# FPGA_POWER_DGND.net
KiCad netlist of a schematic drawn in Altium Designer
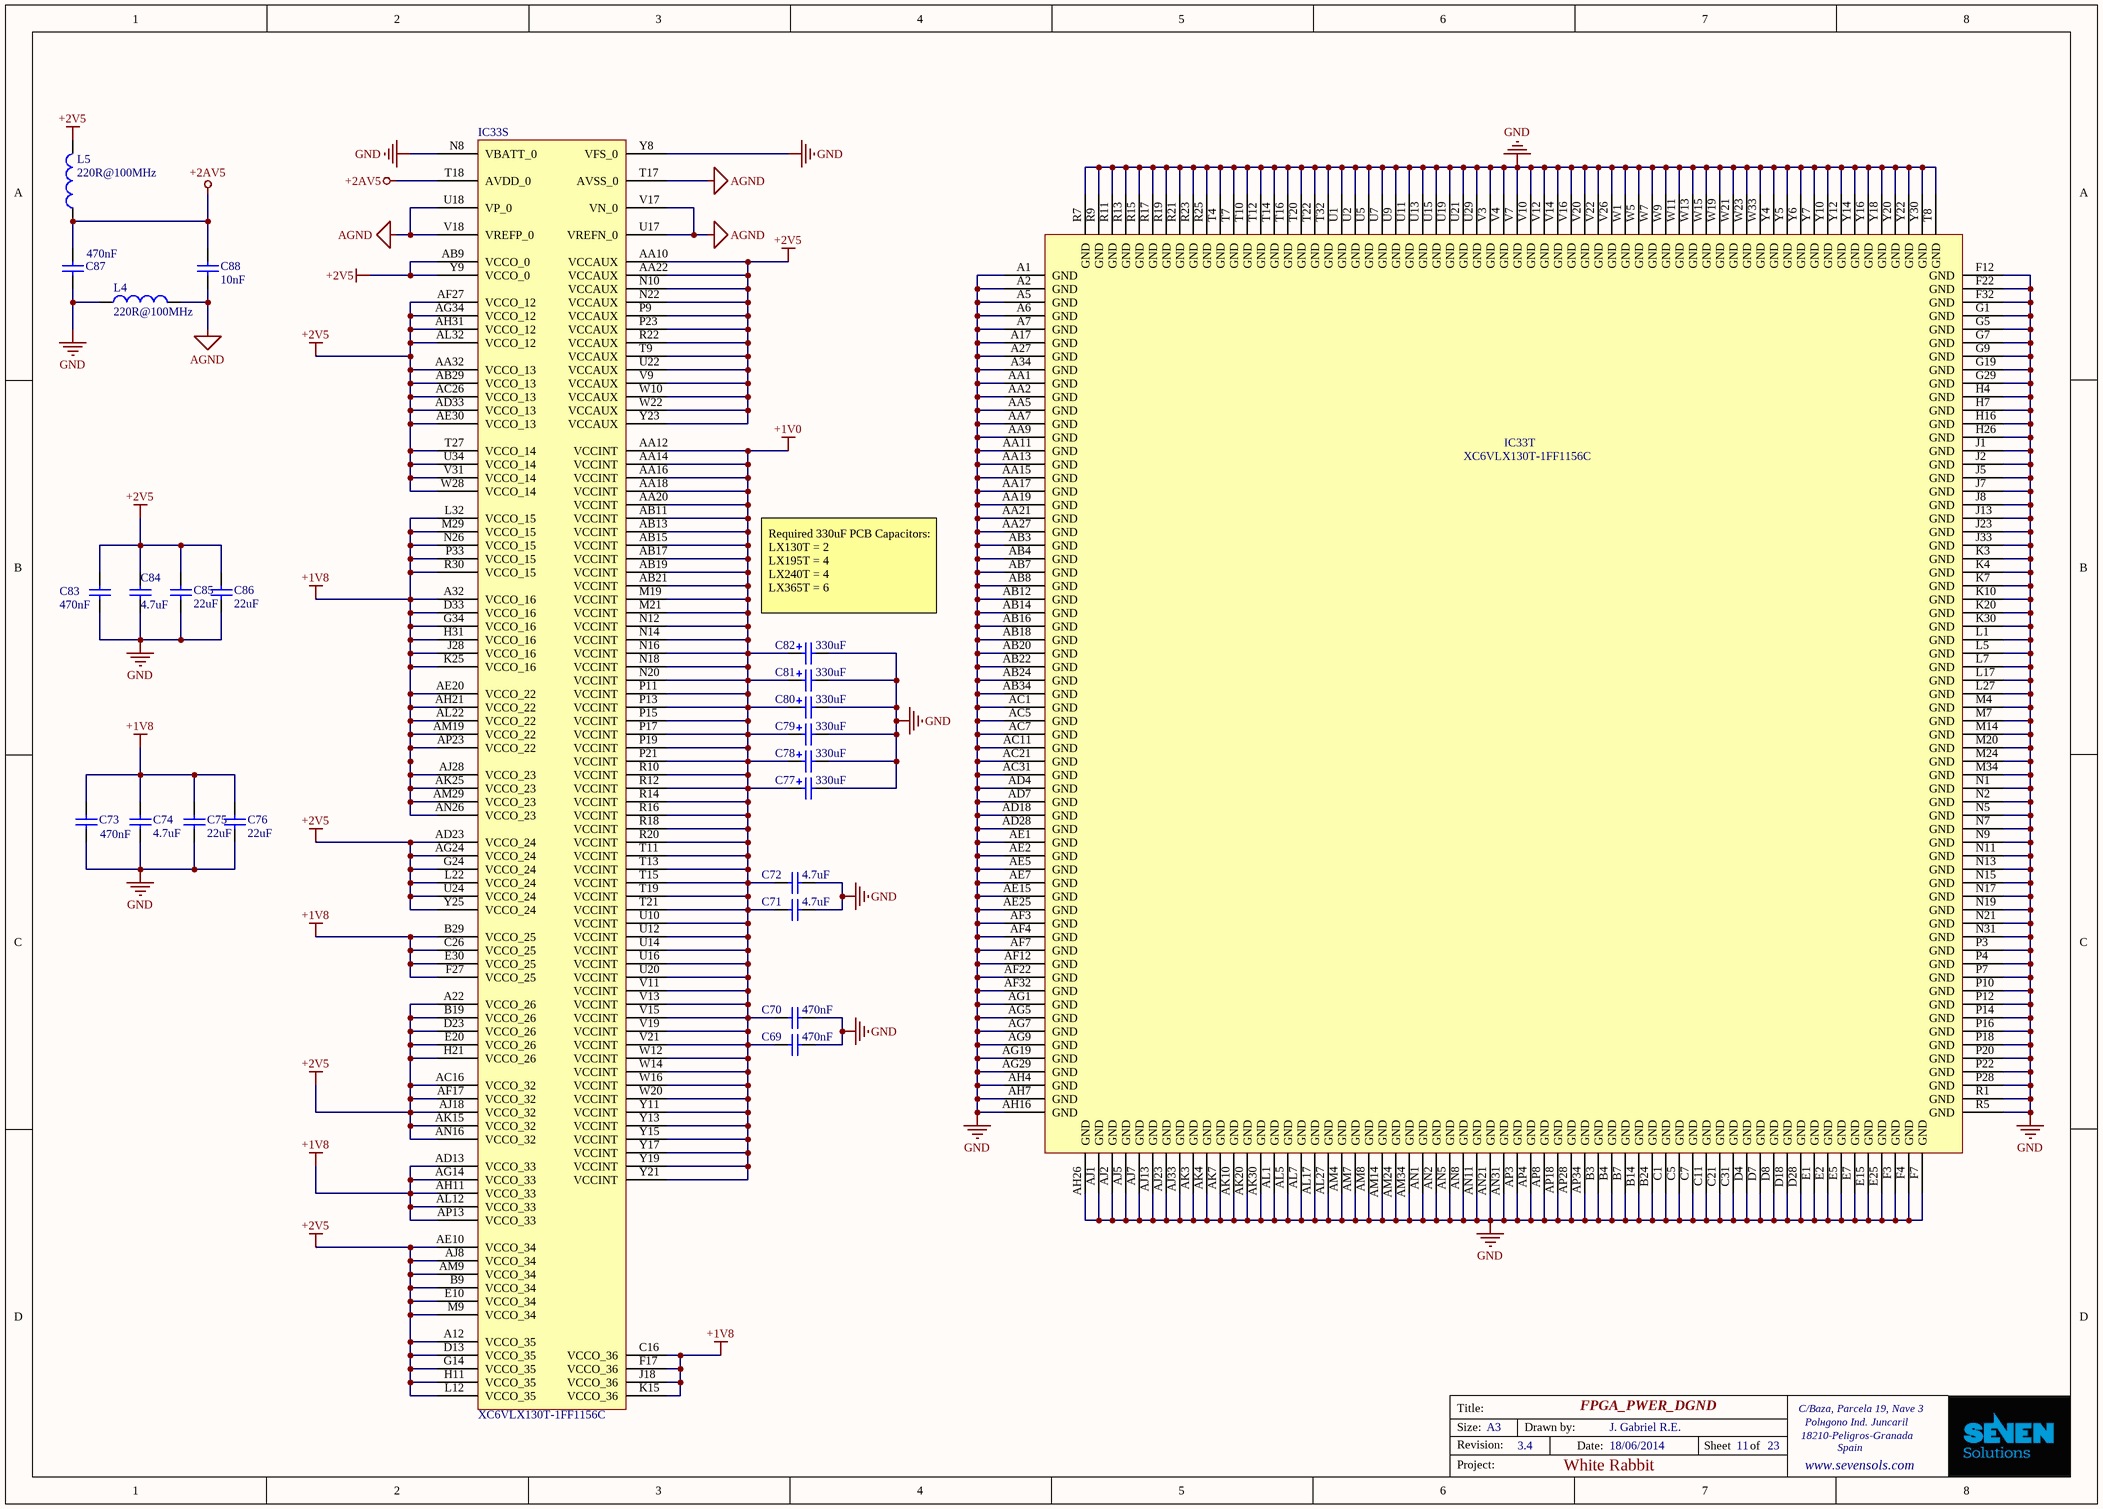
[diagram p0: FPGA_POWER_DGND.SchDoc]

(export (version "E")
  (design (tool "Eeschema 10.0.6"))
  (components
    (comp (ref "C69")
      (value "470nF")
      (footprint "CC1005-0402")
      (description "Capacitor")
      (fields
        (field (name "TOLERANCE") "±10%")
        (field (name "VOLTAGE") "16V")
        (field (name "PUBLISHER") "Altium Limited")
      )
      (libsource (lib "wr_switch") (part "Cap"))
    )
    (comp (ref "C70")
      (value "470nF")
      (footprint "CC1005-0402")
      (description "Capacitor")
      (fields
        (field (name "TOLERANCE") "±10%")
        (field (name "VOLTAGE") "16V")
        (field (name "PUBLISHER") "Altium Limited")
      )
      (libsource (lib "wr_switch") (part "Cap"))
    )
    (comp (ref "C71")
      (value "4.7uF")
      (footprint "CC1608-0603")
      (description "Capacitor")
      (fields
        (field (name "TOLERANCE") "±10%")
        (field (name "VOLTAGE") "10V")
        (field (name "PUBLISHER") "Altium Limited")
      )
      (libsource (lib "wr_switch") (part "Cap"))
    )
    (comp (ref "C72")
      (value "4.7uF")
      (footprint "CC1608-0603")
      (description "Capacitor")
      (fields
        (field (name "TOLERANCE") "±10%")
        (field (name "VOLTAGE") "10V")
        (field (name "PUBLISHER") "Altium Limited")
      )
      (libsource (lib "wr_switch") (part "Cap"))
    )
    (comp (ref "C73")
      (value "470nF")
      (footprint "CC1005-0402")
      (description "Capacitor")
      (fields
        (field (name "TOLERANCE") "±10%")
        (field (name "VOLTAGE") "16V")
        (field (name "PUBLISHER") "Altium Limited")
      )
      (libsource (lib "wr_switch") (part "Cap"))
    )
    (comp (ref "C74")
      (value "4.7uF")
      (footprint "CC1608-0603")
      (description "Capacitor")
      (fields
        (field (name "TOLERANCE") "±10%")
        (field (name "VOLTAGE") "10V")
        (field (name "PUBLISHER") "Altium Limited")
      )
      (libsource (lib "wr_switch") (part "Cap"))
    )
    (comp (ref "C75")
      (value "22uF")
      (footprint "CC2012-0805")
      (description "Capacitor")
      (fields
        (field (name "TOLERANCE") "±20%")
        (field (name "VOLTAGE") "6.3V")
        (field (name "PUBLISHER") "Altium Limited")
      )
      (libsource (lib "wr_switch") (part "Cap"))
    )
    (comp (ref "C76")
      (value "22uF")
      (footprint "CC2012-0805")
      (description "Capacitor")
      (fields
        (field (name "TOLERANCE") "±20%")
        (field (name "VOLTAGE") "6.3V")
        (field (name "PUBLISHER") "Altium Limited")
      )
      (libsource (lib "wr_switch") (part "Cap"))
    )
    (comp (ref "C77")
      (value "330uF")
      (footprint "D")
      (description "Polarized Capacitor Tantalum")
      (fields
        (field (name "TOLERANCE") "±20%")
        (field (name "VOLTAGE") "6.3V")
        (field (name "PUBLISHER") "Altium Limited")
      )
      (libsource (lib "wr_switch") (part "Cap Pol1"))
    )
    (comp (ref "C78")
      (value "330uF")
      (footprint "D")
      (description "Polarized Capacitor Tantalum")
      (fields
        (field (name "TOLERANCE") "±20%")
        (field (name "VOLTAGE") "6.3V")
        (field (name "PUBLISHER") "Altium Limited")
      )
      (libsource (lib "wr_switch") (part "Cap Pol1"))
    )
    (comp (ref "C79")
      (value "330uF")
      (footprint "D")
      (description "Polarized Capacitor Tantalum")
      (fields
        (field (name "TOLERANCE") "±20%")
        (field (name "VOLTAGE") "6.3V")
        (field (name "PUBLISHER") "Altium Limited")
      )
      (libsource (lib "wr_switch") (part "Cap Pol1"))
    )
    (comp (ref "C80")
      (value "330uF")
      (footprint "D")
      (description "Polarized Capacitor Tantalum")
      (fields
        (field (name "TOLERANCE") "±20%")
        (field (name "VOLTAGE") "6.3V")
        (field (name "PUBLISHER") "Altium Limited")
      )
      (libsource (lib "wr_switch") (part "Cap Pol1"))
    )
    (comp (ref "C81")
      (value "330uF")
      (footprint "D")
      (description "Polarized Capacitor Tantalum")
      (fields
        (field (name "TOLERANCE") "±20%")
        (field (name "VOLTAGE") "6.3V")
        (field (name "PUBLISHER") "Altium Limited")
      )
      (libsource (lib "wr_switch") (part "Cap Pol1"))
    )
    (comp (ref "C82")
      (value "330uF")
      (footprint "D")
      (description "Polarized Capacitor Tantalum")
      (fields
        (field (name "TOLERANCE") "±20%")
        (field (name "VOLTAGE") "6.3V")
        (field (name "PUBLISHER") "Altium Limited")
      )
      (libsource (lib "wr_switch") (part "Cap Pol1"))
    )
    (comp (ref "C83")
      (value "470nF")
      (footprint "CC1005-0402")
      (description "Capacitor")
      (fields
        (field (name "TOLERANCE") "±10%")
        (field (name "VOLTAGE") "16V")
        (field (name "PUBLISHER") "Altium Limited")
      )
      (libsource (lib "wr_switch") (part "Cap"))
    )
    (comp (ref "C84")
      (value "4.7uF")
      (footprint "CC1608-0603")
      (description "Capacitor")
      (fields
        (field (name "TOLERANCE") "±10%")
        (field (name "VOLTAGE") "10V")
        (field (name "PUBLISHER") "Altium Limited")
      )
      (libsource (lib "wr_switch") (part "Cap"))
    )
    (comp (ref "C85")
      (value "22uF")
      (footprint "CC2012-0805")
      (description "Capacitor")
      (fields
        (field (name "TOLERANCE") "±20%")
        (field (name "VOLTAGE") "6.3V")
        (field (name "PUBLISHER") "Altium Limited")
      )
      (libsource (lib "wr_switch") (part "Cap"))
    )
    (comp (ref "C86")
      (value "22uF")
      (footprint "CC2012-0805")
      (description "Capacitor")
      (fields
        (field (name "TOLERANCE") "±20%")
        (field (name "VOLTAGE") "6.3V")
        (field (name "PUBLISHER") "Altium Limited")
      )
      (libsource (lib "wr_switch") (part "Cap"))
    )
    (comp (ref "C87")
      (value "470nF")
      (footprint "CC1005-0402")
      (description "Capacitor")
      (fields
        (field (name "TOLERANCE") "±10%")
        (field (name "VOLTAGE") "16V")
        (field (name "PUBLISHER") "Altium Limited")
      )
      (libsource (lib "wr_switch") (part "Cap"))
    )
    (comp (ref "C88")
      (value "10nF")
      (footprint "CC1005-0402")
      (description "Capacitor")
      (fields
        (field (name "TOLERANCE") "±10%")
        (field (name "VOLTAGE") "25V")
        (field (name "PUBLISHER") "Altium Limited")
      )
      (libsource (lib "wr_switch") (part "Cap"))
    )
    (comp (ref "IC33")
      (value "XC6VLX130T-1FF1156C")
      (footprint "FF1156")
      (fields (field (name "PUBLISHER") "Altium Limited"))
      (libsource (lib "Xilinx Virtex-6") (part "XC6VLX130T-1FF1156C"))
    )
    (comp (ref "L4")
      (value "220R@100MHz Ferrite Bead")
      (footprint "0603")
      (description "ferrite bead")
      (fields (field (name "IMPEDANCE") "220R@100MHz"))
      (libsource (lib "wr_switch") (part "L_FERRITE_BEAD"))
    )
    (comp (ref "L5")
      (value "220R@100MHz Ferrite Bead")
      (footprint "0603")
      (description "ferrite bead")
      (fields (field (name "IMPEDANCE") "220R@100MHz"))
      (libsource (lib "wr_switch") (part "L_FERRITE_BEAD"))
    )
  )
  (nets
    (net (code "1") (name "+1V0") (class "Default")
      (node (ref "C69") (pin "2") (pinfunction "2_2") (pintype "passive"))
      (node (ref "C70") (pin "2") (pinfunction "2_2") (pintype "passive"))
      (node (ref "C71") (pin "1") (pinfunction "1_1") (pintype "passive"))
      (node (ref "C72") (pin "1") (pinfunction "1_1") (pintype "passive"))
      (node (ref "C77") (pin "1") (pinfunction "1_1") (pintype "passive"))
      (node (ref "C78") (pin "1") (pinfunction "1_1") (pintype "passive"))
      (node (ref "C79") (pin "1") (pinfunction "1_1") (pintype "passive"))
      (node (ref "C80") (pin "1") (pinfunction "1_1") (pintype "passive"))
      (node (ref "C81") (pin "1") (pinfunction "1_1") (pintype "passive"))
      (node (ref "C82") (pin "1") (pinfunction "1_1") (pintype "passive"))
      (node (ref "IC33") (pin "AA12") (pinfunction "VCCINT_AA12") (pintype "power_in"))
      (node (ref "IC33") (pin "AA14") (pinfunction "VCCINT_AA14") (pintype "power_in"))
      (node (ref "IC33") (pin "AA16") (pinfunction "VCCINT_AA16") (pintype "power_in"))
      (node (ref "IC33") (pin "AA18") (pinfunction "VCCINT_AA18") (pintype "power_in"))
      (node (ref "IC33") (pin "AA20") (pinfunction "VCCINT_AA20") (pintype "power_in"))
      (node (ref "IC33") (pin "AB11") (pinfunction "VCCINT_AB11") (pintype "power_in"))
      (node (ref "IC33") (pin "AB13") (pinfunction "VCCINT_AB13") (pintype "power_in"))
      (node (ref "IC33") (pin "AB15") (pinfunction "VCCINT_AB15") (pintype "power_in"))
      (node (ref "IC33") (pin "AB17") (pinfunction "VCCINT_AB17") (pintype "power_in"))
      (node (ref "IC33") (pin "AB19") (pinfunction "VCCINT_AB19") (pintype "power_in"))
      (node (ref "IC33") (pin "AB21") (pinfunction "VCCINT_AB21") (pintype "power_in"))
      (node (ref "IC33") (pin "M19") (pinfunction "VCCINT_M19") (pintype "power_in"))
      (node (ref "IC33") (pin "M21") (pinfunction "VCCINT_M21") (pintype "power_in"))
      (node (ref "IC33") (pin "N12") (pinfunction "VCCINT_N12") (pintype "power_in"))
      (node (ref "IC33") (pin "N14") (pinfunction "VCCINT_N14") (pintype "power_in"))
      (node (ref "IC33") (pin "N16") (pinfunction "VCCINT_N16") (pintype "power_in"))
      (node (ref "IC33") (pin "N18") (pinfunction "VCCINT_N18") (pintype "power_in"))
      (node (ref "IC33") (pin "N20") (pinfunction "VCCINT_N20") (pintype "power_in"))
      (node (ref "IC33") (pin "P11") (pinfunction "VCCINT_P11") (pintype "power_in"))
      (node (ref "IC33") (pin "P13") (pinfunction "VCCINT_P13") (pintype "power_in"))
      (node (ref "IC33") (pin "P15") (pinfunction "VCCINT_P15") (pintype "power_in"))
      (node (ref "IC33") (pin "P17") (pinfunction "VCCINT_P17") (pintype "power_in"))
      (node (ref "IC33") (pin "P19") (pinfunction "VCCINT_P19") (pintype "power_in"))
      (node (ref "IC33") (pin "P21") (pinfunction "VCCINT_P21") (pintype "power_in"))
      (node (ref "IC33") (pin "R10") (pinfunction "VCCINT_R10") (pintype "power_in"))
      (node (ref "IC33") (pin "R12") (pinfunction "VCCINT_R12") (pintype "power_in"))
      (node (ref "IC33") (pin "R14") (pinfunction "VCCINT_R14") (pintype "power_in"))
      (node (ref "IC33") (pin "R16") (pinfunction "VCCINT_R16") (pintype "power_in"))
      (node (ref "IC33") (pin "R18") (pinfunction "VCCINT_R18") (pintype "power_in"))
      (node (ref "IC33") (pin "R20") (pinfunction "VCCINT_R20") (pintype "power_in"))
      (node (ref "IC33") (pin "T11") (pinfunction "VCCINT_T11") (pintype "power_in"))
      (node (ref "IC33") (pin "T13") (pinfunction "VCCINT_T13") (pintype "power_in"))
      (node (ref "IC33") (pin "T15") (pinfunction "VCCINT_T15") (pintype "power_in"))
      (node (ref "IC33") (pin "T19") (pinfunction "VCCINT_T19") (pintype "power_in"))
      (node (ref "IC33") (pin "T21") (pinfunction "VCCINT_T21") (pintype "power_in"))
      (node (ref "IC33") (pin "U10") (pinfunction "VCCINT_U10") (pintype "power_in"))
      (node (ref "IC33") (pin "U12") (pinfunction "VCCINT_U12") (pintype "power_in"))
      (node (ref "IC33") (pin "U14") (pinfunction "VCCINT_U14") (pintype "power_in"))
      (node (ref "IC33") (pin "U16") (pinfunction "VCCINT_U16") (pintype "power_in"))
      (node (ref "IC33") (pin "U20") (pinfunction "VCCINT_U20") (pintype "power_in"))
      (node (ref "IC33") (pin "V11") (pinfunction "VCCINT_V11") (pintype "power_in"))
      (node (ref "IC33") (pin "V13") (pinfunction "VCCINT_V13") (pintype "power_in"))
      (node (ref "IC33") (pin "V15") (pinfunction "VCCINT_V15") (pintype "power_in"))
      (node (ref "IC33") (pin "V19") (pinfunction "VCCINT_V19") (pintype "power_in"))
      (node (ref "IC33") (pin "V21") (pinfunction "VCCINT_V21") (pintype "power_in"))
      (node (ref "IC33") (pin "W12") (pinfunction "VCCINT_W12") (pintype "power_in"))
      (node (ref "IC33") (pin "W14") (pinfunction "VCCINT_W14") (pintype "power_in"))
      (node (ref "IC33") (pin "W16") (pinfunction "VCCINT_W16") (pintype "power_in"))
      (node (ref "IC33") (pin "W20") (pinfunction "VCCINT_W20") (pintype "power_in"))
      (node (ref "IC33") (pin "Y11") (pinfunction "VCCINT_Y11") (pintype "power_in"))
      (node (ref "IC33") (pin "Y13") (pinfunction "VCCINT_Y13") (pintype "power_in"))
      (node (ref "IC33") (pin "Y15") (pinfunction "VCCINT_Y15") (pintype "power_in"))
      (node (ref "IC33") (pin "Y17") (pinfunction "VCCINT_Y17") (pintype "power_in"))
      (node (ref "IC33") (pin "Y19") (pinfunction "VCCINT_Y19") (pintype "power_in"))
      (node (ref "IC33") (pin "Y21") (pinfunction "VCCINT_Y21") (pintype "power_in"))
    )
    (net (code "2") (name "+1V8") (class "Default")
      (node (ref "C73") (pin "1") (pinfunction "1_1") (pintype "passive"))
      (node (ref "C74") (pin "2") (pinfunction "2_2") (pintype "passive"))
      (node (ref "C75") (pin "2") (pinfunction "2_2") (pintype "passive"))
      (node (ref "C76") (pin "2") (pinfunction "2_2") (pintype "passive"))
      (node (ref "IC33") (pin "A32") (pinfunction "VCCO_16_A32") (pintype "power_in"))
      (node (ref "IC33") (pin "AD13") (pinfunction "VCCO_33_AD13") (pintype "power_in"))
      (node (ref "IC33") (pin "AE20") (pinfunction "VCCO_22_AE20") (pintype "power_in"))
      (node (ref "IC33") (pin "AG14") (pinfunction "VCCO_33_AG14") (pintype "power_in"))
      (node (ref "IC33") (pin "AH11") (pinfunction "VCCO_33_AH11") (pintype "power_in"))
      (node (ref "IC33") (pin "AH21") (pinfunction "VCCO_22_AH21") (pintype "power_in"))
      (node (ref "IC33") (pin "AJ28") (pinfunction "VCCO_23_AJ28") (pintype "power_in"))
      (node (ref "IC33") (pin "AK25") (pinfunction "VCCO_23_AK25") (pintype "power_in"))
      (node (ref "IC33") (pin "AL12") (pinfunction "VCCO_33_AL12") (pintype "power_in"))
      (node (ref "IC33") (pin "AL22") (pinfunction "VCCO_22_AL22") (pintype "power_in"))
      (node (ref "IC33") (pin "AM19") (pinfunction "VCCO_22_AM19") (pintype "power_in"))
      (node (ref "IC33") (pin "AM29") (pinfunction "VCCO_23_AM29") (pintype "power_in"))
      (node (ref "IC33") (pin "AN26") (pinfunction "VCCO_23_AN26") (pintype "power_in"))
      (node (ref "IC33") (pin "AP13") (pinfunction "VCCO_33_AP13") (pintype "power_in"))
      (node (ref "IC33") (pin "AP23") (pinfunction "VCCO_22_AP23") (pintype "power_in"))
      (node (ref "IC33") (pin "B29") (pinfunction "VCCO_25_B29") (pintype "power_in"))
      (node (ref "IC33") (pin "C16") (pinfunction "VCCO_36_C16") (pintype "power_in"))
      (node (ref "IC33") (pin "C26") (pinfunction "VCCO_25_C26") (pintype "power_in"))
      (node (ref "IC33") (pin "D33") (pinfunction "VCCO_16_D33") (pintype "power_in"))
      (node (ref "IC33") (pin "E30") (pinfunction "VCCO_25_E30") (pintype "power_in"))
      (node (ref "IC33") (pin "F17") (pinfunction "VCCO_36_F17") (pintype "power_in"))
      (node (ref "IC33") (pin "F27") (pinfunction "VCCO_25_F27") (pintype "power_in"))
      (node (ref "IC33") (pin "G34") (pinfunction "VCCO_16_G34") (pintype "power_in"))
      (node (ref "IC33") (pin "H31") (pinfunction "VCCO_16_H31") (pintype "power_in"))
      (node (ref "IC33") (pin "J18") (pinfunction "VCCO_36_J18") (pintype "power_in"))
      (node (ref "IC33") (pin "J28") (pinfunction "VCCO_16_J28") (pintype "power_in"))
      (node (ref "IC33") (pin "K15") (pinfunction "VCCO_36_K15") (pintype "power_in"))
      (node (ref "IC33") (pin "K25") (pinfunction "VCCO_16_K25") (pintype "power_in"))
      (node (ref "IC33") (pin "L32") (pinfunction "VCCO_15_L32") (pintype "power_in"))
      (node (ref "IC33") (pin "M29") (pinfunction "VCCO_15_M29") (pintype "power_in"))
      (node (ref "IC33") (pin "N26") (pinfunction "VCCO_15_N26") (pintype "power_in"))
      (node (ref "IC33") (pin "P33") (pinfunction "VCCO_15_P33") (pintype "power_in"))
      (node (ref "IC33") (pin "R30") (pinfunction "VCCO_15_R30") (pintype "power_in"))
    )
    (net (code "3") (name "+2AV5") (class "Default")
      (node (ref "C87") (pin "1") (pinfunction "1_1") (pintype "passive"))
      (node (ref "C88") (pin "1") (pinfunction "1_1") (pintype "passive"))
      (node (ref "IC33") (pin "T18") (pinfunction "AVDD_0_T18") (pintype "power_in"))
      (node (ref "L5") (pin "1") (pinfunction "1_1") (pintype "passive"))
    )
    (net (code "4") (name "+2V5") (class "Default")
      (node (ref "C83") (pin "1") (pinfunction "1_1") (pintype "passive"))
      (node (ref "C84") (pin "2") (pinfunction "2_2") (pintype "passive"))
      (node (ref "C85") (pin "2") (pinfunction "2_2") (pintype "passive"))
      (node (ref "C86") (pin "2") (pinfunction "2_2") (pintype "passive"))
      (node (ref "IC33") (pin "A12") (pinfunction "VCCO_35_A12") (pintype "power_in"))
      (node (ref "IC33") (pin "A22") (pinfunction "VCCO_26_A22") (pintype "power_in"))
      (node (ref "IC33") (pin "AA10") (pinfunction "VCCAUX_AA10") (pintype "power_in"))
      (node (ref "IC33") (pin "AA22") (pinfunction "VCCAUX_AA22") (pintype "power_in"))
      (node (ref "IC33") (pin "AA32") (pinfunction "VCCO_13_AA32") (pintype "power_in"))
      (node (ref "IC33") (pin "AB29") (pinfunction "VCCO_13_AB29") (pintype "power_in"))
      (node (ref "IC33") (pin "AB9") (pinfunction "VCCO_0_AB9") (pintype "power_in"))
      (node (ref "IC33") (pin "AC16") (pinfunction "VCCO_32_AC16") (pintype "power_in"))
      (node (ref "IC33") (pin "AC26") (pinfunction "VCCO_13_AC26") (pintype "power_in"))
      (node (ref "IC33") (pin "AD23") (pinfunction "VCCO_24_AD23") (pintype "power_in"))
      (node (ref "IC33") (pin "AD33") (pinfunction "VCCO_13_AD33") (pintype "power_in"))
      (node (ref "IC33") (pin "AE10") (pinfunction "VCCO_34_AE10") (pintype "power_in"))
      (node (ref "IC33") (pin "AE30") (pinfunction "VCCO_13_AE30") (pintype "power_in"))
      (node (ref "IC33") (pin "AF17") (pinfunction "VCCO_32_AF17") (pintype "power_in"))
      (node (ref "IC33") (pin "AF27") (pinfunction "VCCO_12_AF27") (pintype "power_in"))
      (node (ref "IC33") (pin "AG24") (pinfunction "VCCO_24_AG24") (pintype "power_in"))
      (node (ref "IC33") (pin "AG34") (pinfunction "VCCO_12_AG34") (pintype "power_in"))
      (node (ref "IC33") (pin "AH31") (pinfunction "VCCO_12_AH31") (pintype "power_in"))
      (node (ref "IC33") (pin "AJ18") (pinfunction "VCCO_32_AJ18") (pintype "power_in"))
      (node (ref "IC33") (pin "AJ8") (pinfunction "VCCO_34_AJ8") (pintype "power_in"))
      (node (ref "IC33") (pin "AK15") (pinfunction "VCCO_32_AK15") (pintype "power_in"))
      (node (ref "IC33") (pin "AL32") (pinfunction "VCCO_12_AL32") (pintype "power_in"))
      (node (ref "IC33") (pin "AM9") (pinfunction "VCCO_34_AM9") (pintype "power_in"))
      (node (ref "IC33") (pin "AN16") (pinfunction "VCCO_32_AN16") (pintype "power_in"))
      (node (ref "IC33") (pin "B19") (pinfunction "VCCO_26_B19") (pintype "power_in"))
      (node (ref "IC33") (pin "B9") (pinfunction "VCCO_34_B9") (pintype "power_in"))
      (node (ref "IC33") (pin "D13") (pinfunction "VCCO_35_D13") (pintype "power_in"))
      (node (ref "IC33") (pin "D23") (pinfunction "VCCO_26_D23") (pintype "power_in"))
      (node (ref "IC33") (pin "E10") (pinfunction "VCCO_34_E10") (pintype "power_in"))
      (node (ref "IC33") (pin "E20") (pinfunction "VCCO_26_E20") (pintype "power_in"))
      (node (ref "IC33") (pin "G14") (pinfunction "VCCO_35_G14") (pintype "power_in"))
      (node (ref "IC33") (pin "G24") (pinfunction "VCCO_24_G24") (pintype "power_in"))
      (node (ref "IC33") (pin "H11") (pinfunction "VCCO_35_H11") (pintype "power_in"))
      (node (ref "IC33") (pin "H21") (pinfunction "VCCO_26_H21") (pintype "power_in"))
      (node (ref "IC33") (pin "L12") (pinfunction "VCCO_35_L12") (pintype "power_in"))
      (node (ref "IC33") (pin "L22") (pinfunction "VCCO_24_L22") (pintype "power_in"))
      (node (ref "IC33") (pin "M9") (pinfunction "VCCO_34_M9") (pintype "power_in"))
      (node (ref "IC33") (pin "N10") (pinfunction "VCCAUX_N10") (pintype "power_in"))
      (node (ref "IC33") (pin "N22") (pinfunction "VCCAUX_N22") (pintype "power_in"))
      (node (ref "IC33") (pin "P23") (pinfunction "VCCAUX_P23") (pintype "power_in"))
      (node (ref "IC33") (pin "P9") (pinfunction "VCCAUX_P9") (pintype "power_in"))
      (node (ref "IC33") (pin "R22") (pinfunction "VCCAUX_R22") (pintype "power_in"))
      (node (ref "IC33") (pin "T27") (pinfunction "VCCO_14_T27") (pintype "power_in"))
      (node (ref "IC33") (pin "T9") (pinfunction "VCCAUX_T9") (pintype "power_in"))
      (node (ref "IC33") (pin "U22") (pinfunction "VCCAUX_U22") (pintype "power_in"))
      (node (ref "IC33") (pin "U24") (pinfunction "VCCO_24_U24") (pintype "power_in"))
      (node (ref "IC33") (pin "U34") (pinfunction "VCCO_14_U34") (pintype "power_in"))
      (node (ref "IC33") (pin "V31") (pinfunction "VCCO_14_V31") (pintype "power_in"))
      (node (ref "IC33") (pin "V9") (pinfunction "VCCAUX_V9") (pintype "power_in"))
      (node (ref "IC33") (pin "W10") (pinfunction "VCCAUX_W10") (pintype "power_in"))
      (node (ref "IC33") (pin "W22") (pinfunction "VCCAUX_W22") (pintype "power_in"))
      (node (ref "IC33") (pin "W28") (pinfunction "VCCO_14_W28") (pintype "power_in"))
      (node (ref "IC33") (pin "Y23") (pinfunction "VCCAUX_Y23") (pintype "power_in"))
      (node (ref "IC33") (pin "Y25") (pinfunction "VCCO_24_Y25") (pintype "power_in"))
      (node (ref "IC33") (pin "Y9") (pinfunction "VCCO_0_Y9") (pintype "power_in"))
      (node (ref "L5") (pin "2") (pinfunction "2_2") (pintype "passive"))
    )
    (net (code "5") (name "AGND") (class "Default")
      (node (ref "C88") (pin "2") (pinfunction "2_2") (pintype "passive"))
      (node (ref "IC33") (pin "T17") (pinfunction "AVSS_0_T17") (pintype "power_in"))
      (node (ref "IC33") (pin "U17") (pinfunction "VREFN_0_U17") (pintype "power_in"))
      (node (ref "IC33") (pin "U18") (pinfunction "VP_0_U18") (pintype "power_in"))
      (node (ref "IC33") (pin "V17") (pinfunction "VN_0_V17") (pintype "power_in"))
      (node (ref "IC33") (pin "V18") (pinfunction "VREFP_0_V18") (pintype "power_in"))
      (node (ref "L4") (pin "2") (pinfunction "2_2") (pintype "passive"))
    )
    (net (code "6") (name "GND") (class "Default")
      (node (ref "C69") (pin "1") (pinfunction "1_1") (pintype "passive"))
      (node (ref "C70") (pin "1") (pinfunction "1_1") (pintype "passive"))
      (node (ref "C71") (pin "2") (pinfunction "2_2") (pintype "passive"))
      (node (ref "C72") (pin "2") (pinfunction "2_2") (pintype "passive"))
      (node (ref "C73") (pin "2") (pinfunction "2_2") (pintype "passive"))
      (node (ref "C74") (pin "1") (pinfunction "1_1") (pintype "passive"))
      (node (ref "C75") (pin "1") (pinfunction "1_1") (pintype "passive"))
      (node (ref "C76") (pin "1") (pinfunction "1_1") (pintype "passive"))
      (node (ref "C77") (pin "2") (pinfunction "2_2") (pintype "passive"))
      (node (ref "C78") (pin "2") (pinfunction "2_2") (pintype "passive"))
      (node (ref "C79") (pin "2") (pinfunction "2_2") (pintype "passive"))
      (node (ref "C80") (pin "2") (pinfunction "2_2") (pintype "passive"))
      (node (ref "C81") (pin "2") (pinfunction "2_2") (pintype "passive"))
      (node (ref "C82") (pin "2") (pinfunction "2_2") (pintype "passive"))
      (node (ref "C83") (pin "2") (pinfunction "2_2") (pintype "passive"))
      (node (ref "C84") (pin "1") (pinfunction "1_1") (pintype "passive"))
      (node (ref "C85") (pin "1") (pinfunction "1_1") (pintype "passive"))
      (node (ref "C86") (pin "1") (pinfunction "1_1") (pintype "passive"))
      (node (ref "C87") (pin "2") (pinfunction "2_2") (pintype "passive"))
      (node (ref "IC33") (pin "A1") (pinfunction "GND_A1") (pintype "power_in"))
      (node (ref "IC33") (pin "A17") (pinfunction "GND_A17") (pintype "power_in"))
      (node (ref "IC33") (pin "A2") (pinfunction "GND_A2") (pintype "power_in"))
      (node (ref "IC33") (pin "A27") (pinfunction "GND_A27") (pintype "power_in"))
      (node (ref "IC33") (pin "A34") (pinfunction "GND_A34") (pintype "power_in"))
      (node (ref "IC33") (pin "A5") (pinfunction "GND_A5") (pintype "power_in"))
      (node (ref "IC33") (pin "A6") (pinfunction "GND_A6") (pintype "power_in"))
      (node (ref "IC33") (pin "A7") (pinfunction "GND_A7") (pintype "power_in"))
      (node (ref "IC33") (pin "AA1") (pinfunction "GND_AA1") (pintype "power_in"))
      (node (ref "IC33") (pin "AA11") (pinfunction "GND_AA11") (pintype "power_in"))
      (node (ref "IC33") (pin "AA13") (pinfunction "GND_AA13") (pintype "power_in"))
      (node (ref "IC33") (pin "AA15") (pinfunction "GND_AA15") (pintype "power_in"))
      (node (ref "IC33") (pin "AA17") (pinfunction "GND_AA17") (pintype "power_in"))
      (node (ref "IC33") (pin "AA19") (pinfunction "GND_AA19") (pintype "power_in"))
      (node (ref "IC33") (pin "AA2") (pinfunction "GND_AA2") (pintype "power_in"))
      (node (ref "IC33") (pin "AA21") (pinfunction "GND_AA21") (pintype "power_in"))
      (node (ref "IC33") (pin "AA27") (pinfunction "GND_AA27") (pintype "power_in"))
      (node (ref "IC33") (pin "AA5") (pinfunction "GND_AA5") (pintype "power_in"))
      (node (ref "IC33") (pin "AA7") (pinfunction "GND_AA7") (pintype "power_in"))
      (node (ref "IC33") (pin "AA9") (pinfunction "GND_AA9") (pintype "power_in"))
      (node (ref "IC33") (pin "AB12") (pinfunction "GND_AB12") (pintype "power_in"))
      (node (ref "IC33") (pin "AB14") (pinfunction "GND_AB14") (pintype "power_in"))
      (node (ref "IC33") (pin "AB16") (pinfunction "GND_AB16") (pintype "power_in"))
      (node (ref "IC33") (pin "AB18") (pinfunction "GND_AB18") (pintype "power_in"))
      (node (ref "IC33") (pin "AB20") (pinfunction "GND_AB20") (pintype "power_in"))
      (node (ref "IC33") (pin "AB22") (pinfunction "GND_AB22") (pintype "power_in"))
      (node (ref "IC33") (pin "AB24") (pinfunction "GND_AB24") (pintype "power_in"))
      (node (ref "IC33") (pin "AB3") (pinfunction "GND_AB3") (pintype "power_in"))
      (node (ref "IC33") (pin "AB34") (pinfunction "GND_AB34") (pintype "power_in"))
      (node (ref "IC33") (pin "AB4") (pinfunction "GND_AB4") (pintype "power_in"))
      (node (ref "IC33") (pin "AB7") (pinfunction "GND_AB7") (pintype "power_in"))
      (node (ref "IC33") (pin "AB8") (pinfunction "GND_AB8") (pintype "power_in"))
      (node (ref "IC33") (pin "AC1") (pinfunction "GND_AC1") (pintype "power_in"))
      (node (ref "IC33") (pin "AC11") (pinfunction "GND_AC11") (pintype "power_in"))
      (node (ref "IC33") (pin "AC21") (pinfunction "GND_AC21") (pintype "power_in"))
      (node (ref "IC33") (pin "AC31") (pinfunction "GND_AC31") (pintype "power_in"))
      (node (ref "IC33") (pin "AC5") (pinfunction "GND_AC5") (pintype "power_in"))
      (node (ref "IC33") (pin "AC7") (pinfunction "GND_AC7") (pintype "power_in"))
      (node (ref "IC33") (pin "AD18") (pinfunction "GND_AD18") (pintype "power_in"))
      (node (ref "IC33") (pin "AD28") (pinfunction "GND_AD28") (pintype "power_in"))
      (node (ref "IC33") (pin "AD4") (pinfunction "GND_AD4") (pintype "power_in"))
      (node (ref "IC33") (pin "AD7") (pinfunction "GND_AD7") (pintype "power_in"))
      (node (ref "IC33") (pin "AE1") (pinfunction "GND_AE1") (pintype "power_in"))
      (node (ref "IC33") (pin "AE15") (pinfunction "GND_AE15") (pintype "power_in"))
      (node (ref "IC33") (pin "AE2") (pinfunction "GND_AE2") (pintype "power_in"))
      (node (ref "IC33") (pin "AE25") (pinfunction "GND_AE25") (pintype "power_in"))
      (node (ref "IC33") (pin "AE5") (pinfunction "GND_AE5") (pintype "power_in"))
      (node (ref "IC33") (pin "AE7") (pinfunction "GND_AE7") (pintype "power_in"))
      (node (ref "IC33") (pin "AF12") (pinfunction "GND_AF12") (pintype "power_in"))
      (node (ref "IC33") (pin "AF22") (pinfunction "GND_AF22") (pintype "power_in"))
      (node (ref "IC33") (pin "AF3") (pinfunction "GND_AF3") (pintype "power_in"))
      (node (ref "IC33") (pin "AF32") (pinfunction "GND_AF32") (pintype "power_in"))
      (node (ref "IC33") (pin "AF4") (pinfunction "GND_AF4") (pintype "power_in"))
      (node (ref "IC33") (pin "AF7") (pinfunction "GND_AF7") (pintype "power_in"))
      (node (ref "IC33") (pin "AG1") (pinfunction "GND_AG1") (pintype "power_in"))
      (node (ref "IC33") (pin "AG19") (pinfunction "GND_AG19") (pintype "power_in"))
      (node (ref "IC33") (pin "AG29") (pinfunction "GND_AG29") (pintype "power_in"))
      (node (ref "IC33") (pin "AG5") (pinfunction "GND_AG5") (pintype "power_in"))
      (node (ref "IC33") (pin "AG7") (pinfunction "GND_AG7") (pintype "power_in"))
      (node (ref "IC33") (pin "AG9") (pinfunction "GND_AG9") (pintype "power_in"))
      (node (ref "IC33") (pin "AH16") (pinfunction "GND_AH16") (pintype "power_in"))
      (node (ref "IC33") (pin "AH26") (pinfunction "GND_AH26") (pintype "power_in"))
      (node (ref "IC33") (pin "AH4") (pinfunction "GND_AH4") (pintype "power_in"))
      (node (ref "IC33") (pin "AH7") (pinfunction "GND_AH7") (pintype "power_in"))
      (node (ref "IC33") (pin "AJ1") (pinfunction "GND_AJ1") (pintype "power_in"))
      (node (ref "IC33") (pin "AJ13") (pinfunction "GND_AJ13") (pintype "power_in"))
      (node (ref "IC33") (pin "AJ2") (pinfunction "GND_AJ2") (pintype "power_in"))
      (node (ref "IC33") (pin "AJ23") (pinfunction "GND_AJ23") (pintype "power_in"))
      (node (ref "IC33") (pin "AJ33") (pinfunction "GND_AJ33") (pintype "power_in"))
      (node (ref "IC33") (pin "AJ5") (pinfunction "GND_AJ5") (pintype "power_in"))
      (node (ref "IC33") (pin "AJ7") (pinfunction "GND_AJ7") (pintype "power_in"))
      (node (ref "IC33") (pin "AK10") (pinfunction "GND_AK10") (pintype "power_in"))
      (node (ref "IC33") (pin "AK20") (pinfunction "GND_AK20") (pintype "power_in"))
      (node (ref "IC33") (pin "AK3") (pinfunction "GND_AK3") (pintype "power_in"))
      (node (ref "IC33") (pin "AK30") (pinfunction "GND_AK30") (pintype "power_in"))
      (node (ref "IC33") (pin "AK4") (pinfunction "GND_AK4") (pintype "power_in"))
      (node (ref "IC33") (pin "AK7") (pinfunction "GND_AK7") (pintype "power_in"))
      (node (ref "IC33") (pin "AL1") (pinfunction "GND_AL1") (pintype "power_in"))
      (node (ref "IC33") (pin "AL17") (pinfunction "GND_AL17") (pintype "power_in"))
      (node (ref "IC33") (pin "AL27") (pinfunction "GND_AL27") (pintype "power_in"))
      (node (ref "IC33") (pin "AL5") (pinfunction "GND_AL5") (pintype "power_in"))
      (node (ref "IC33") (pin "AL7") (pinfunction "GND_AL7") (pintype "power_in"))
      (node (ref "IC33") (pin "AM14") (pinfunction "GND_AM14") (pintype "power_in"))
      (node (ref "IC33") (pin "AM24") (pinfunction "GND_AM24") (pintype "power_in"))
      (node (ref "IC33") (pin "AM34") (pinfunction "GND_AM34") (pintype "power_in"))
      (node (ref "IC33") (pin "AM4") (pinfunction "GND_AM4") (pintype "power_in"))
      (node (ref "IC33") (pin "AM7") (pinfunction "GND_AM7") (pintype "power_in"))
      (node (ref "IC33") (pin "AM8") (pinfunction "GND_AM8") (pintype "power_in"))
      (node (ref "IC33") (pin "AN1") (pinfunction "GND_AN1") (pintype "power_in"))
      (node (ref "IC33") (pin "AN11") (pinfunction "GND_AN11") (pintype "power_in"))
      (node (ref "IC33") (pin "AN2") (pinfunction "GND_AN2") (pintype "power_in"))
      (node (ref "IC33") (pin "AN21") (pinfunction "GND_AN21") (pintype "power_in"))
      (node (ref "IC33") (pin "AN31") (pinfunction "GND_AN31") (pintype "power_in"))
      (node (ref "IC33") (pin "AN5") (pinfunction "GND_AN5") (pintype "power_in"))
      (node (ref "IC33") (pin "AN8") (pinfunction "GND_AN8") (pintype "power_in"))
      (node (ref "IC33") (pin "AP18") (pinfunction "GND_AP18") (pintype "power_in"))
      (node (ref "IC33") (pin "AP28") (pinfunction "GND_AP28") (pintype "power_in"))
      (node (ref "IC33") (pin "AP3") (pinfunction "GND_AP3") (pintype "power_in"))
      (node (ref "IC33") (pin "AP34") (pinfunction "GND_AP34") (pintype "power_in"))
      (node (ref "IC33") (pin "AP4") (pinfunction "GND_AP4") (pintype "power_in"))
      (node (ref "IC33") (pin "AP8") (pinfunction "GND_AP8") (pintype "power_in"))
      (node (ref "IC33") (pin "B14") (pinfunction "GND_B14") (pintype "power_in"))
      (node (ref "IC33") (pin "B24") (pinfunction "GND_B24") (pintype "power_in"))
      (node (ref "IC33") (pin "B3") (pinfunction "GND_B3") (pintype "power_in"))
      (node (ref "IC33") (pin "B4") (pinfunction "GND_B4") (pintype "power_in"))
      (node (ref "IC33") (pin "B7") (pinfunction "GND_B7") (pintype "power_in"))
      (node (ref "IC33") (pin "C1") (pinfunction "GND_C1") (pintype "power_in"))
      (node (ref "IC33") (pin "C11") (pinfunction "GND_C11") (pintype "power_in"))
      (node (ref "IC33") (pin "C21") (pinfunction "GND_C21") (pintype "power_in"))
      (node (ref "IC33") (pin "C31") (pinfunction "GND_C31") (pintype "power_in"))
      (node (ref "IC33") (pin "C5") (pinfunction "GND_C5") (pintype "power_in"))
      (node (ref "IC33") (pin "C7") (pinfunction "GND_C7") (pintype "power_in"))
      (node (ref "IC33") (pin "D18") (pinfunction "GND_D18") (pintype "power_in"))
      (node (ref "IC33") (pin "D28") (pinfunction "GND_D28") (pintype "power_in"))
      (node (ref "IC33") (pin "D4") (pinfunction "GND_D4") (pintype "power_in"))
      (node (ref "IC33") (pin "D7") (pinfunction "GND_D7") (pintype "power_in"))
      (node (ref "IC33") (pin "D8") (pinfunction "GND_D8") (pintype "power_in"))
      (node (ref "IC33") (pin "E1") (pinfunction "GND_E1") (pintype "power_in"))
      (node (ref "IC33") (pin "E15") (pinfunction "GND_E15") (pintype "power_in"))
      (node (ref "IC33") (pin "E2") (pinfunction "GND_E2") (pintype "power_in"))
      (node (ref "IC33") (pin "E25") (pinfunction "GND_E25") (pintype "power_in"))
      (node (ref "IC33") (pin "E5") (pinfunction "GND_E5") (pintype "power_in"))
      (node (ref "IC33") (pin "E7") (pinfunction "GND_E7") (pintype "power_in"))
      (node (ref "IC33") (pin "F12") (pinfunction "GND_F12") (pintype "power_in"))
      (node (ref "IC33") (pin "F22") (pinfunction "GND_F22") (pintype "power_in"))
      (node (ref "IC33") (pin "F3") (pinfunction "GND_F3") (pintype "power_in"))
      (node (ref "IC33") (pin "F32") (pinfunction "GND_F32") (pintype "power_in"))
      (node (ref "IC33") (pin "F4") (pinfunction "GND_F4") (pintype "power_in"))
      (node (ref "IC33") (pin "F7") (pinfunction "GND_F7") (pintype "power_in"))
      (node (ref "IC33") (pin "G1") (pinfunction "GND_G1") (pintype "power_in"))
      (node (ref "IC33") (pin "G19") (pinfunction "GND_G19") (pintype "power_in"))
      (node (ref "IC33") (pin "G29") (pinfunction "GND_G29") (pintype "power_in"))
      (node (ref "IC33") (pin "G5") (pinfunction "GND_G5") (pintype "power_in"))
      (node (ref "IC33") (pin "G7") (pinfunction "GND_G7") (pintype "power_in"))
      (node (ref "IC33") (pin "G9") (pinfunction "GND_G9") (pintype "power_in"))
      (node (ref "IC33") (pin "H16") (pinfunction "GND_H16") (pintype "power_in"))
      (node (ref "IC33") (pin "H26") (pinfunction "GND_H26") (pintype "power_in"))
      (node (ref "IC33") (pin "H4") (pinfunction "GND_H4") (pintype "power_in"))
      (node (ref "IC33") (pin "H7") (pinfunction "GND_H7") (pintype "power_in"))
      (node (ref "IC33") (pin "J1") (pinfunction "GND_J1") (pintype "power_in"))
      (node (ref "IC33") (pin "J13") (pinfunction "GND_J13") (pintype "power_in"))
      (node (ref "IC33") (pin "J2") (pinfunction "GND_J2") (pintype "power_in"))
      (node (ref "IC33") (pin "J23") (pinfunction "GND_J23") (pintype "power_in"))
      (node (ref "IC33") (pin "J33") (pinfunction "GND_J33") (pintype "power_in"))
      (node (ref "IC33") (pin "J5") (pinfunction "GND_J5") (pintype "power_in"))
      (node (ref "IC33") (pin "J7") (pinfunction "GND_J7") (pintype "power_in"))
      (node (ref "IC33") (pin "J8") (pinfunction "GND_J8") (pintype "power_in"))
      (node (ref "IC33") (pin "K10") (pinfunction "GND_K10") (pintype "power_in"))
      (node (ref "IC33") (pin "K20") (pinfunction "GND_K20") (pintype "power_in"))
      (node (ref "IC33") (pin "K3") (pinfunction "GND_K3") (pintype "power_in"))
      (node (ref "IC33") (pin "K30") (pinfunction "GND_K30") (pintype "power_in"))
      (node (ref "IC33") (pin "K4") (pinfunction "GND_K4") (pintype "power_in"))
      (node (ref "IC33") (pin "K7") (pinfunction "GND_K7") (pintype "power_in"))
      (node (ref "IC33") (pin "L1") (pinfunction "GND_L1") (pintype "power_in"))
      (node (ref "IC33") (pin "L17") (pinfunction "GND_L17") (pintype "power_in"))
      (node (ref "IC33") (pin "L27") (pinfunction "GND_L27") (pintype "power_in"))
      (node (ref "IC33") (pin "L5") (pinfunction "GND_L5") (pintype "power_in"))
      (node (ref "IC33") (pin "L7") (pinfunction "GND_L7") (pintype "power_in"))
      (node (ref "IC33") (pin "M14") (pinfunction "GND_M14") (pintype "power_in"))
      (node (ref "IC33") (pin "M20") (pinfunction "GND_M20") (pintype "power_in"))
      (node (ref "IC33") (pin "M24") (pinfunction "GND_M24") (pintype "power_in"))
      (node (ref "IC33") (pin "M34") (pinfunction "GND_M34") (pintype "power_in"))
      (node (ref "IC33") (pin "M4") (pinfunction "GND_M4") (pintype "power_in"))
      (node (ref "IC33") (pin "M7") (pinfunction "GND_M7") (pintype "power_in"))
      (node (ref "IC33") (pin "N1") (pinfunction "GND_N1") (pintype "power_in"))
      (node (ref "IC33") (pin "N11") (pinfunction "GND_N11") (pintype "power_in"))
      (node (ref "IC33") (pin "N13") (pinfunction "GND_N13") (pintype "power_in"))
      (node (ref "IC33") (pin "N15") (pinfunction "GND_N15") (pintype "power_in"))
      (node (ref "IC33") (pin "N17") (pinfunction "GND_N17") (pintype "power_in"))
      (node (ref "IC33") (pin "N19") (pinfunction "GND_N19") (pintype "power_in"))
      (node (ref "IC33") (pin "N2") (pinfunction "GND_N2") (pintype "power_in"))
      (node (ref "IC33") (pin "N21") (pinfunction "GND_N21") (pintype "power_in"))
      (node (ref "IC33") (pin "N31") (pinfunction "GND_N31") (pintype "power_in"))
      (node (ref "IC33") (pin "N5") (pinfunction "GND_N5") (pintype "power_in"))
      (node (ref "IC33") (pin "N7") (pinfunction "GND_N7") (pintype "power_in"))
      (node (ref "IC33") (pin "N8") (pinfunction "VBATT_0_N8") (pintype "power_in"))
      (node (ref "IC33") (pin "N9") (pinfunction "GND_N9") (pintype "power_in"))
      (node (ref "IC33") (pin "P10") (pinfunction "GND_P10") (pintype "power_in"))
      (node (ref "IC33") (pin "P12") (pinfunction "GND_P12") (pintype "power_in"))
      (node (ref "IC33") (pin "P14") (pinfunction "GND_P14") (pintype "power_in"))
      (node (ref "IC33") (pin "P16") (pinfunction "GND_P16") (pintype "power_in"))
      (node (ref "IC33") (pin "P18") (pinfunction "GND_P18") (pintype "power_in"))
      (node (ref "IC33") (pin "P20") (pinfunction "GND_P20") (pintype "power_in"))
      (node (ref "IC33") (pin "P22") (pinfunction "GND_P22") (pintype "power_in"))
      (node (ref "IC33") (pin "P28") (pinfunction "GND_P28") (pintype "power_in"))
      (node (ref "IC33") (pin "P3") (pinfunction "GND_P3") (pintype "power_in"))
      (node (ref "IC33") (pin "P4") (pinfunction "GND_P4") (pintype "power_in"))
      (node (ref "IC33") (pin "P7") (pinfunction "GND_P7") (pintype "power_in"))
      (node (ref "IC33") (pin "R1") (pinfunction "GND_R1") (pintype "power_in"))
      (node (ref "IC33") (pin "R11") (pinfunction "GND_R11") (pintype "power_in"))
      (node (ref "IC33") (pin "R13") (pinfunction "GND_R13") (pintype "power_in"))
      (node (ref "IC33") (pin "R15") (pinfunction "GND_R15") (pintype "power_in"))
      (node (ref "IC33") (pin "R17") (pinfunction "GND_R17") (pintype "power_in"))
      (node (ref "IC33") (pin "R19") (pinfunction "GND_R19") (pintype "power_in"))
      (node (ref "IC33") (pin "R21") (pinfunction "GND_R21") (pintype "power_in"))
      (node (ref "IC33") (pin "R23") (pinfunction "GND_R23") (pintype "power_in"))
      (node (ref "IC33") (pin "R25") (pinfunction "GND_R25") (pintype "power_in"))
      (node (ref "IC33") (pin "R5") (pinfunction "GND_R5") (pintype "power_in"))
      (node (ref "IC33") (pin "R7") (pinfunction "GND_R7") (pintype "power_in"))
      (node (ref "IC33") (pin "R9") (pinfunction "GND_R9") (pintype "power_in"))
      (node (ref "IC33") (pin "T10") (pinfunction "GND_T10") (pintype "power_in"))
      (node (ref "IC33") (pin "T12") (pinfunction "GND_T12") (pintype "power_in"))
      (node (ref "IC33") (pin "T14") (pinfunction "GND_T14") (pintype "power_in"))
      (node (ref "IC33") (pin "T16") (pinfunction "GND_T16") (pintype "power_in"))
      (node (ref "IC33") (pin "T20") (pinfunction "GND_T20") (pintype "power_in"))
      (node (ref "IC33") (pin "T22") (pinfunction "GND_T22") (pintype "power_in"))
      (node (ref "IC33") (pin "T32") (pinfunction "GND_T32") (pintype "power_in"))
      (node (ref "IC33") (pin "T4") (pinfunction "GND_T4") (pintype "power_in"))
      (node (ref "IC33") (pin "T7") (pinfunction "GND_T7") (pintype "power_in"))
      (node (ref "IC33") (pin "T8") (pinfunction "GND_T8") (pintype "power_in"))
      (node (ref "IC33") (pin "U1") (pinfunction "GND_U1") (pintype "power_in"))
      (node (ref "IC33") (pin "U11") (pinfunction "GND_U11") (pintype "power_in"))
      (node (ref "IC33") (pin "U13") (pinfunction "GND_U13") (pintype "power_in"))
      (node (ref "IC33") (pin "U15") (pinfunction "GND_U15") (pintype "power_in"))
      (node (ref "IC33") (pin "U19") (pinfunction "GND_U19") (pintype "power_in"))
      (node (ref "IC33") (pin "U2") (pinfunction "GND_U2") (pintype "power_in"))
      (node (ref "IC33") (pin "U21") (pinfunction "GND_U21") (pintype "power_in"))
      (node (ref "IC33") (pin "U29") (pinfunction "GND_U29") (pintype "power_in"))
      (node (ref "IC33") (pin "U5") (pinfunction "GND_U5") (pintype "power_in"))
      (node (ref "IC33") (pin "U7") (pinfunction "GND_U7") (pintype "power_in"))
      (node (ref "IC33") (pin "U9") (pinfunction "GND_U9") (pintype "power_in"))
      (node (ref "IC33") (pin "V10") (pinfunction "GND_V10") (pintype "power_in"))
      (node (ref "IC33") (pin "V12") (pinfunction "GND_V12") (pintype "power_in"))
      (node (ref "IC33") (pin "V14") (pinfunction "GND_V14") (pintype "power_in"))
      (node (ref "IC33") (pin "V16") (pinfunction "GND_V16") (pintype "power_in"))
      (node (ref "IC33") (pin "V20") (pinfunction "GND_V20") (pintype "power_in"))
      (node (ref "IC33") (pin "V22") (pinfunction "GND_V22") (pintype "power_in"))
      (node (ref "IC33") (pin "V26") (pinfunction "GND_V26") (pintype "power_in"))
      (node (ref "IC33") (pin "V3") (pinfunction "GND_V3") (pintype "power_in"))
      (node (ref "IC33") (pin "V4") (pinfunction "GND_V4") (pintype "power_in"))
      (node (ref "IC33") (pin "V7") (pinfunction "GND_V7") (pintype "power_in"))
      (node (ref "IC33") (pin "W1") (pinfunction "GND_W1") (pintype "power_in"))
      (node (ref "IC33") (pin "W11") (pinfunction "GND_W11") (pintype "power_in"))
      (node (ref "IC33") (pin "W13") (pinfunction "GND_W13") (pintype "power_in"))
      (node (ref "IC33") (pin "W15") (pinfunction "GND_W15") (pintype "power_in"))
      (node (ref "IC33") (pin "W19") (pinfunction "GND_W19") (pintype "power_in"))
      (node (ref "IC33") (pin "W21") (pinfunction "GND_W21") (pintype "power_in"))
      (node (ref "IC33") (pin "W23") (pinfunction "GND_W23") (pintype "power_in"))
      (node (ref "IC33") (pin "W33") (pinfunction "GND_W33") (pintype "power_in"))
      (node (ref "IC33") (pin "W5") (pinfunction "GND_W5") (pintype "power_in"))
      (node (ref "IC33") (pin "W7") (pinfunction "GND_W7") (pintype "power_in"))
      (node (ref "IC33") (pin "W9") (pinfunction "GND_W9") (pintype "power_in"))
      (node (ref "IC33") (pin "Y10") (pinfunction "GND_Y10") (pintype "power_in"))
      (node (ref "IC33") (pin "Y12") (pinfunction "GND_Y12") (pintype "power_in"))
      (node (ref "IC33") (pin "Y14") (pinfunction "GND_Y14") (pintype "power_in"))
      (node (ref "IC33") (pin "Y16") (pinfunction "GND_Y16") (pintype "power_in"))
      (node (ref "IC33") (pin "Y18") (pinfunction "GND_Y18") (pintype "power_in"))
      (node (ref "IC33") (pin "Y20") (pinfunction "GND_Y20") (pintype "power_in"))
      (node (ref "IC33") (pin "Y22") (pinfunction "GND_Y22") (pintype "power_in"))
      (node (ref "IC33") (pin "Y30") (pinfunction "GND_Y30") (pintype "power_in"))
      (node (ref "IC33") (pin "Y4") (pinfunction "GND_Y4") (pintype "power_in"))
      (node (ref "IC33") (pin "Y5") (pinfunction "GND_Y5") (pintype "power_in"))
      (node (ref "IC33") (pin "Y6") (pinfunction "GND_Y6") (pintype "power_in"))
      (node (ref "IC33") (pin "Y7") (pinfunction "GND_Y7") (pintype "power_in"))
      (node (ref "IC33") (pin "Y8") (pinfunction "VFS_0_Y8") (pintype "power_in"))
      (node (ref "L4") (pin "1") (pinfunction "1_1") (pintype "passive"))
    )
  )
)
